# 1-Schematic_Meshtastic_Lite.net
KiCad netlist of a schematic drawn in EasyEDA
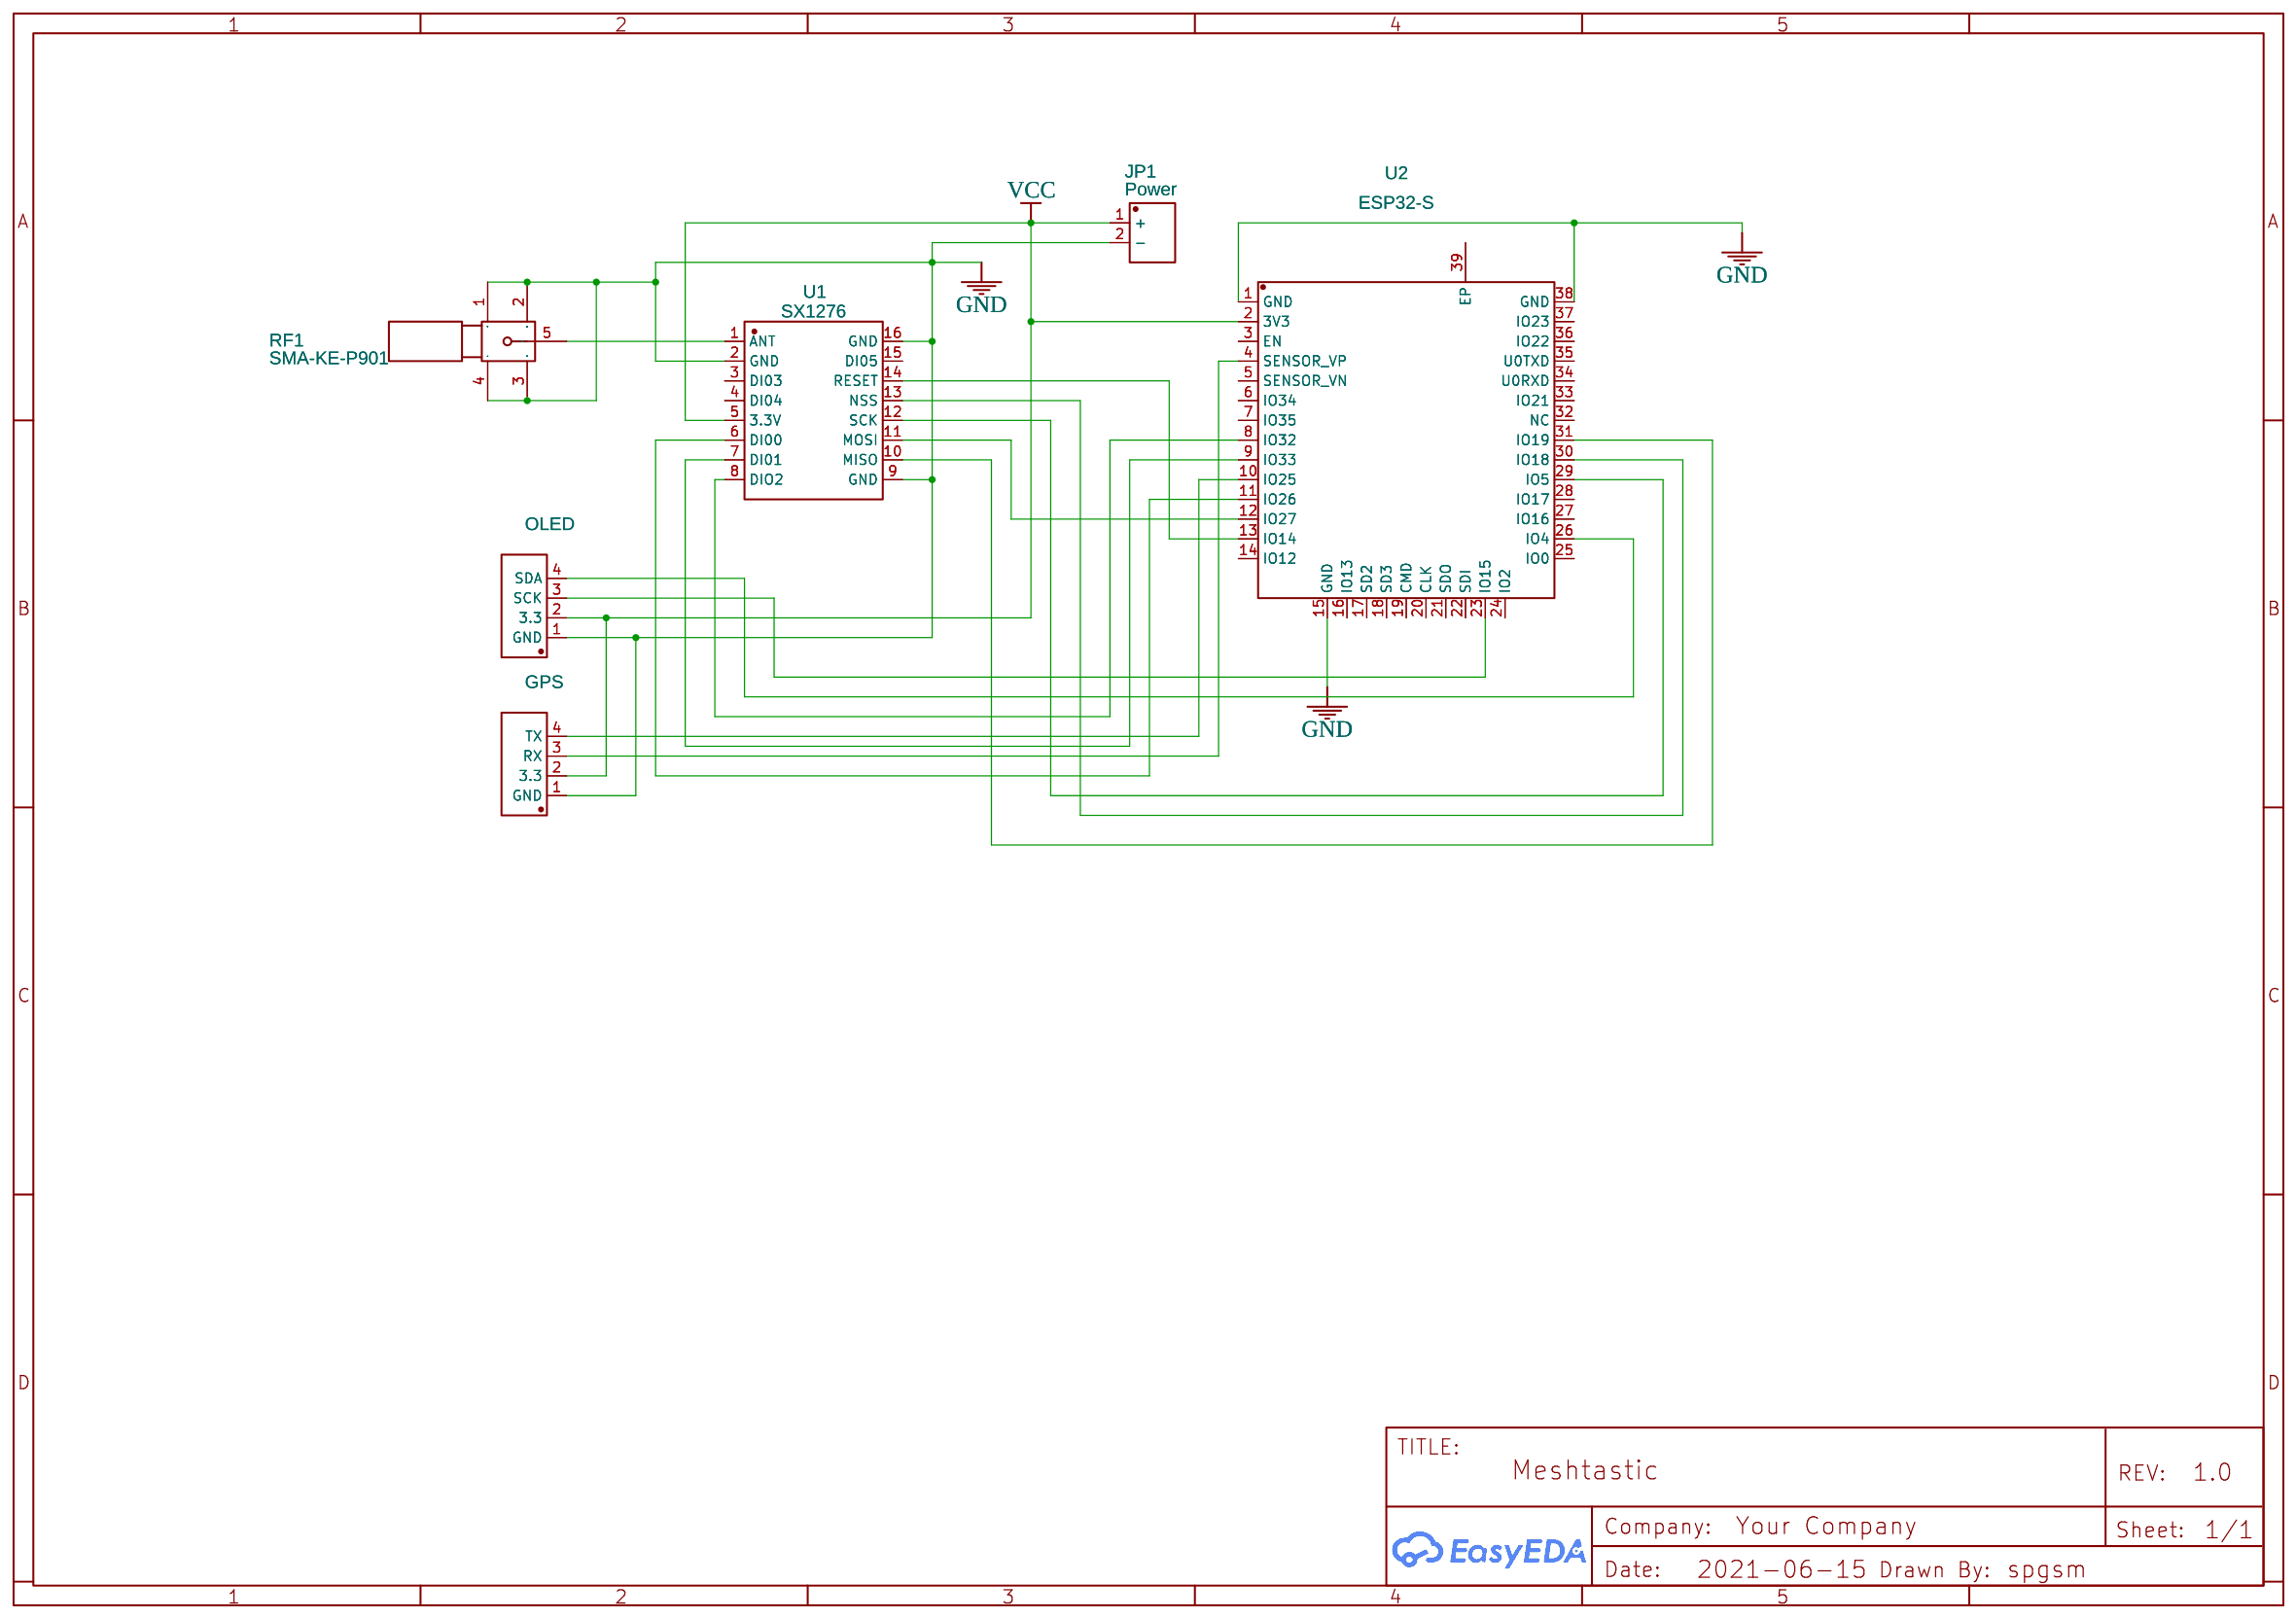
[diagram p0: schematic sheet]

(export (version "E")
  (design (tool "Eeschema 10.0.6"))
  (components
    (comp (ref "GPS")
      (value "GPS")
      (fields (field (name "BOM_Manufacturer Part") "KF2510-4A") (field (name "BOM_Supplier Part") "C27542"))
      (libsource (lib "") (part "KF2510-4A"))
    )
    (comp (ref "JP1")
      (value "Power")
      (fields (field (name "BOM_Manufacturer Part") "1.25T-1-2A") (field (name "BOM_Supplier Part") "C2324"))
      (libsource (lib "") (part "1.25T-1-2A_C2324"))
    )
    (comp (ref "OLED")
      (value "OLED")
      (fields (field (name "BOM_Manufacturer Part") "KF2510-4A") (field (name "BOM_Supplier Part") "C27542"))
      (libsource (lib "") (part "KF2510-4A_1"))
    )
    (comp (ref "RF1")
      (value "SMA-KE-P901")
      (fields (field (name "BOM_Supplier Part") "C914556"))
      (libsource (lib "") (part "SMA-KE-P901"))
    )
    (comp (ref "U1")
      (value "SX1276")
      (fields
        (field (name "BOM_Manufacturer Part") "SX1276S8S+T-X1")
        (field (name "BOM_Supplier Part") "C718834")
      )
      (libsource (lib "") (part "SX1276S8S+T-X1"))
    )
    (comp (ref "U2")
      (value "ESP32-S")
      (fields (field (name "BOM_Supplier Part") "C277944"))
      (libsource (lib "") (part "ESP32-S"))
    )
  )
  (nets
    (net (code "1") (name "GND") (class "Default")
      (node (ref "GPS") (pin "1") (pinfunction "GND_1") (pintype "unspecified"))
      (node (ref "JP1") (pin "2") (pinfunction "-_2") (pintype "unspecified"))
      (node (ref "OLED") (pin "1") (pinfunction "GND_1") (pintype "unspecified"))
      (node (ref "RF1") (pin "1") (pinfunction "1_1") (pintype "unspecified"))
      (node (ref "RF1") (pin "2") (pinfunction "2_2") (pintype "unspecified"))
      (node (ref "RF1") (pin "3") (pinfunction "3_3") (pintype "unspecified"))
      (node (ref "RF1") (pin "4") (pinfunction "4_4") (pintype "unspecified"))
      (node (ref "U1") (pin "16") (pinfunction "GND_16") (pintype "unspecified"))
      (node (ref "U1") (pin "2") (pinfunction "GND_2") (pintype "unspecified"))
      (node (ref "U1") (pin "9") (pinfunction "GND_9") (pintype "unspecified"))
      (node (ref "U2") (pin "1") (pinfunction "GND_1") (pintype "unspecified"))
      (node (ref "U2") (pin "15") (pinfunction "GND_15") (pintype "unspecified"))
      (node (ref "U2") (pin "38") (pinfunction "GND_38") (pintype "unspecified"))
    )
    (net (code "2") (name "Net-(GPS-RX)") (class "Default")
      (node (ref "GPS") (pin "3") (pinfunction "RX_3") (pintype "unspecified"))
      (node (ref "U2") (pin "4") (pinfunction "SENSOR_VP_4") (pintype "unspecified"))
    )
    (net (code "3") (name "Net-(GPS-TX)") (class "Default")
      (node (ref "GPS") (pin "4") (pinfunction "TX_4") (pintype "unspecified"))
      (node (ref "U2") (pin "10") (pinfunction "IO25_10") (pintype "unspecified"))
    )
    (net (code "4") (name "Net-(OLED-SCK)") (class "Default")
      (node (ref "OLED") (pin "3") (pinfunction "SCK_3") (pintype "unspecified"))
      (node (ref "U2") (pin "23") (pinfunction "IO15_23") (pintype "unspecified"))
    )
    (net (code "5") (name "Net-(OLED-SDA)") (class "Default")
      (node (ref "OLED") (pin "4") (pinfunction "SDA_4") (pintype "unspecified"))
      (node (ref "U2") (pin "26") (pinfunction "IO4_26") (pintype "unspecified"))
    )
    (net (code "6") (name "Net-(U1-ANT)") (class "Default")
      (node (ref "RF1") (pin "5") (pinfunction "5_5") (pintype "unspecified"))
      (node (ref "U1") (pin "1") (pinfunction "ANT_1") (pintype "unspecified"))
    )
    (net (code "7") (name "Net-(U1-DI00)") (class "Default")
      (node (ref "U1") (pin "6") (pinfunction "DI00_6") (pintype "unspecified"))
      (node (ref "U2") (pin "11") (pinfunction "IO26_11") (pintype "unspecified"))
    )
    (net (code "8") (name "Net-(U1-DI01)") (class "Default")
      (node (ref "U1") (pin "7") (pinfunction "DI01_7") (pintype "unspecified"))
      (node (ref "U2") (pin "9") (pinfunction "IO33_9") (pintype "unspecified"))
    )
    (net (code "9") (name "Net-(U1-DIO2)") (class "Default")
      (node (ref "U1") (pin "8") (pinfunction "DIO2_8") (pintype "unspecified"))
      (node (ref "U2") (pin "8") (pinfunction "IO32_8") (pintype "unspecified"))
    )
    (net (code "10") (name "Net-(U1-MISO)") (class "Default")
      (node (ref "U1") (pin "10") (pinfunction "MISO_10") (pintype "unspecified"))
      (node (ref "U2") (pin "31") (pinfunction "IO19_31") (pintype "unspecified"))
    )
    (net (code "11") (name "Net-(U1-MOSI)") (class "Default")
      (node (ref "U1") (pin "11") (pinfunction "MOSI_11") (pintype "unspecified"))
      (node (ref "U2") (pin "12") (pinfunction "IO27_12") (pintype "unspecified"))
    )
    (net (code "12") (name "Net-(U1-NSS)") (class "Default")
      (node (ref "U1") (pin "13") (pinfunction "NSS_13") (pintype "unspecified"))
      (node (ref "U2") (pin "30") (pinfunction "IO18_30") (pintype "unspecified"))
    )
    (net (code "13") (name "Net-(U1-RESET)") (class "Default")
      (node (ref "U1") (pin "14") (pinfunction "RESET_14") (pintype "unspecified"))
      (node (ref "U2") (pin "13") (pinfunction "IO14_13") (pintype "unspecified"))
    )
    (net (code "14") (name "Net-(U1-SCK)") (class "Default")
      (node (ref "U1") (pin "12") (pinfunction "SCK_12") (pintype "unspecified"))
      (node (ref "U2") (pin "29") (pinfunction "IO5_29") (pintype "unspecified"))
    )
    (net (code "15") (name "VCC") (class "Default")
      (node (ref "GPS") (pin "2") (pinfunction "3.3_2") (pintype "unspecified"))
      (node (ref "JP1") (pin "1") (pinfunction "+_1") (pintype "unspecified"))
      (node (ref "OLED") (pin "2") (pinfunction "3.3_2") (pintype "unspecified"))
      (node (ref "U1") (pin "5") (pinfunction "3.3V_5") (pintype "unspecified"))
      (node (ref "U2") (pin "2") (pinfunction "3V3_2") (pintype "unspecified"))
    )
    (net (code "16") (name "unconnected-(U1-DI03-Pad3)") (class "Default")
      (node (ref "U1") (pin "3") (pinfunction "DI03_3") (pintype "unspecified"))
    )
    (net (code "17") (name "unconnected-(U1-DI04-Pad4)") (class "Default")
      (node (ref "U1") (pin "4") (pinfunction "DI04_4") (pintype "unspecified"))
    )
    (net (code "18") (name "unconnected-(U1-DI05-Pad15)") (class "Default")
      (node (ref "U1") (pin "15") (pinfunction "DI05_15") (pintype "unspecified"))
    )
    (net (code "19") (name "unconnected-(U2-CLK-Pad20)") (class "Default")
      (node (ref "U2") (pin "20") (pinfunction "CLK_20") (pintype "unspecified"))
    )
    (net (code "20") (name "unconnected-(U2-CMD-Pad19)") (class "Default")
      (node (ref "U2") (pin "19") (pinfunction "CMD_19") (pintype "unspecified"))
    )
    (net (code "21") (name "unconnected-(U2-EN-Pad3)") (class "Default")
      (node (ref "U2") (pin "3") (pinfunction "EN_3") (pintype "unspecified"))
    )
    (net (code "22") (name "unconnected-(U2-EP-Pad39)") (class "Default")
      (node (ref "U2") (pin "39") (pinfunction "EP_39") (pintype "unspecified"))
    )
    (net (code "23") (name "unconnected-(U2-IO0-Pad25)") (class "Default")
      (node (ref "U2") (pin "25") (pinfunction "IO0_25") (pintype "unspecified"))
    )
    (net (code "24") (name "unconnected-(U2-IO2-Pad24)") (class "Default")
      (node (ref "U2") (pin "24") (pinfunction "IO2_24") (pintype "unspecified"))
    )
    (net (code "25") (name "unconnected-(U2-IO12-Pad14)") (class "Default")
      (node (ref "U2") (pin "14") (pinfunction "IO12_14") (pintype "unspecified"))
    )
    (net (code "26") (name "unconnected-(U2-IO13-Pad16)") (class "Default")
      (node (ref "U2") (pin "16") (pinfunction "IO13_16") (pintype "unspecified"))
    )
    (net (code "27") (name "unconnected-(U2-IO16-Pad27)") (class "Default")
      (node (ref "U2") (pin "27") (pinfunction "IO16_27") (pintype "unspecified"))
    )
    (net (code "28") (name "unconnected-(U2-IO17-Pad28)") (class "Default")
      (node (ref "U2") (pin "28") (pinfunction "IO17_28") (pintype "unspecified"))
    )
    (net (code "29") (name "unconnected-(U2-IO21-Pad33)") (class "Default")
      (node (ref "U2") (pin "33") (pinfunction "IO21_33") (pintype "unspecified"))
    )
    (net (code "30") (name "unconnected-(U2-IO22-Pad36)") (class "Default")
      (node (ref "U2") (pin "36") (pinfunction "IO22_36") (pintype "unspecified"))
    )
    (net (code "31") (name "unconnected-(U2-IO23-Pad37)") (class "Default")
      (node (ref "U2") (pin "37") (pinfunction "IO23_37") (pintype "unspecified"))
    )
    (net (code "32") (name "unconnected-(U2-IO34-Pad6)") (class "Default")
      (node (ref "U2") (pin "6") (pinfunction "IO34_6") (pintype "unspecified"))
    )
    (net (code "33") (name "unconnected-(U2-IO35-Pad7)") (class "Default")
      (node (ref "U2") (pin "7") (pinfunction "IO35_7") (pintype "unspecified"))
    )
    (net (code "34") (name "unconnected-(U2-NC-Pad32)") (class "Default")
      (node (ref "U2") (pin "32") (pinfunction "NC_32") (pintype "unspecified"))
    )
    (net (code "35") (name "unconnected-(U2-SD2-Pad17)") (class "Default")
      (node (ref "U2") (pin "17") (pinfunction "SD2_17") (pintype "unspecified"))
    )
    (net (code "36") (name "unconnected-(U2-SD3-Pad18)") (class "Default")
      (node (ref "U2") (pin "18") (pinfunction "SD3_18") (pintype "unspecified"))
    )
    (net (code "37") (name "unconnected-(U2-SDI-Pad22)") (class "Default")
      (node (ref "U2") (pin "22") (pinfunction "SDI_22") (pintype "unspecified"))
    )
    (net (code "38") (name "unconnected-(U2-SDO-Pad21)") (class "Default")
      (node (ref "U2") (pin "21") (pinfunction "SDO_21") (pintype "unspecified"))
    )
    (net (code "39") (name "unconnected-(U2-SENSOR_VN-Pad5)") (class "Default")
      (node (ref "U2") (pin "5") (pinfunction "SENSOR_VN_5") (pintype "unspecified"))
    )
    (net (code "40") (name "unconnected-(U2-U0RXD-Pad34)") (class "Default")
      (node (ref "U2") (pin "34") (pinfunction "U0RXD_34") (pintype "unspecified"))
    )
    (net (code "41") (name "unconnected-(U2-U0TXD-Pad35)") (class "Default")
      (node (ref "U2") (pin "35") (pinfunction "U0TXD_35") (pintype "unspecified"))
    )
  )
)
